# Minisumo_V1.net
KiCad netlist of a schematic drawn in EAGLE
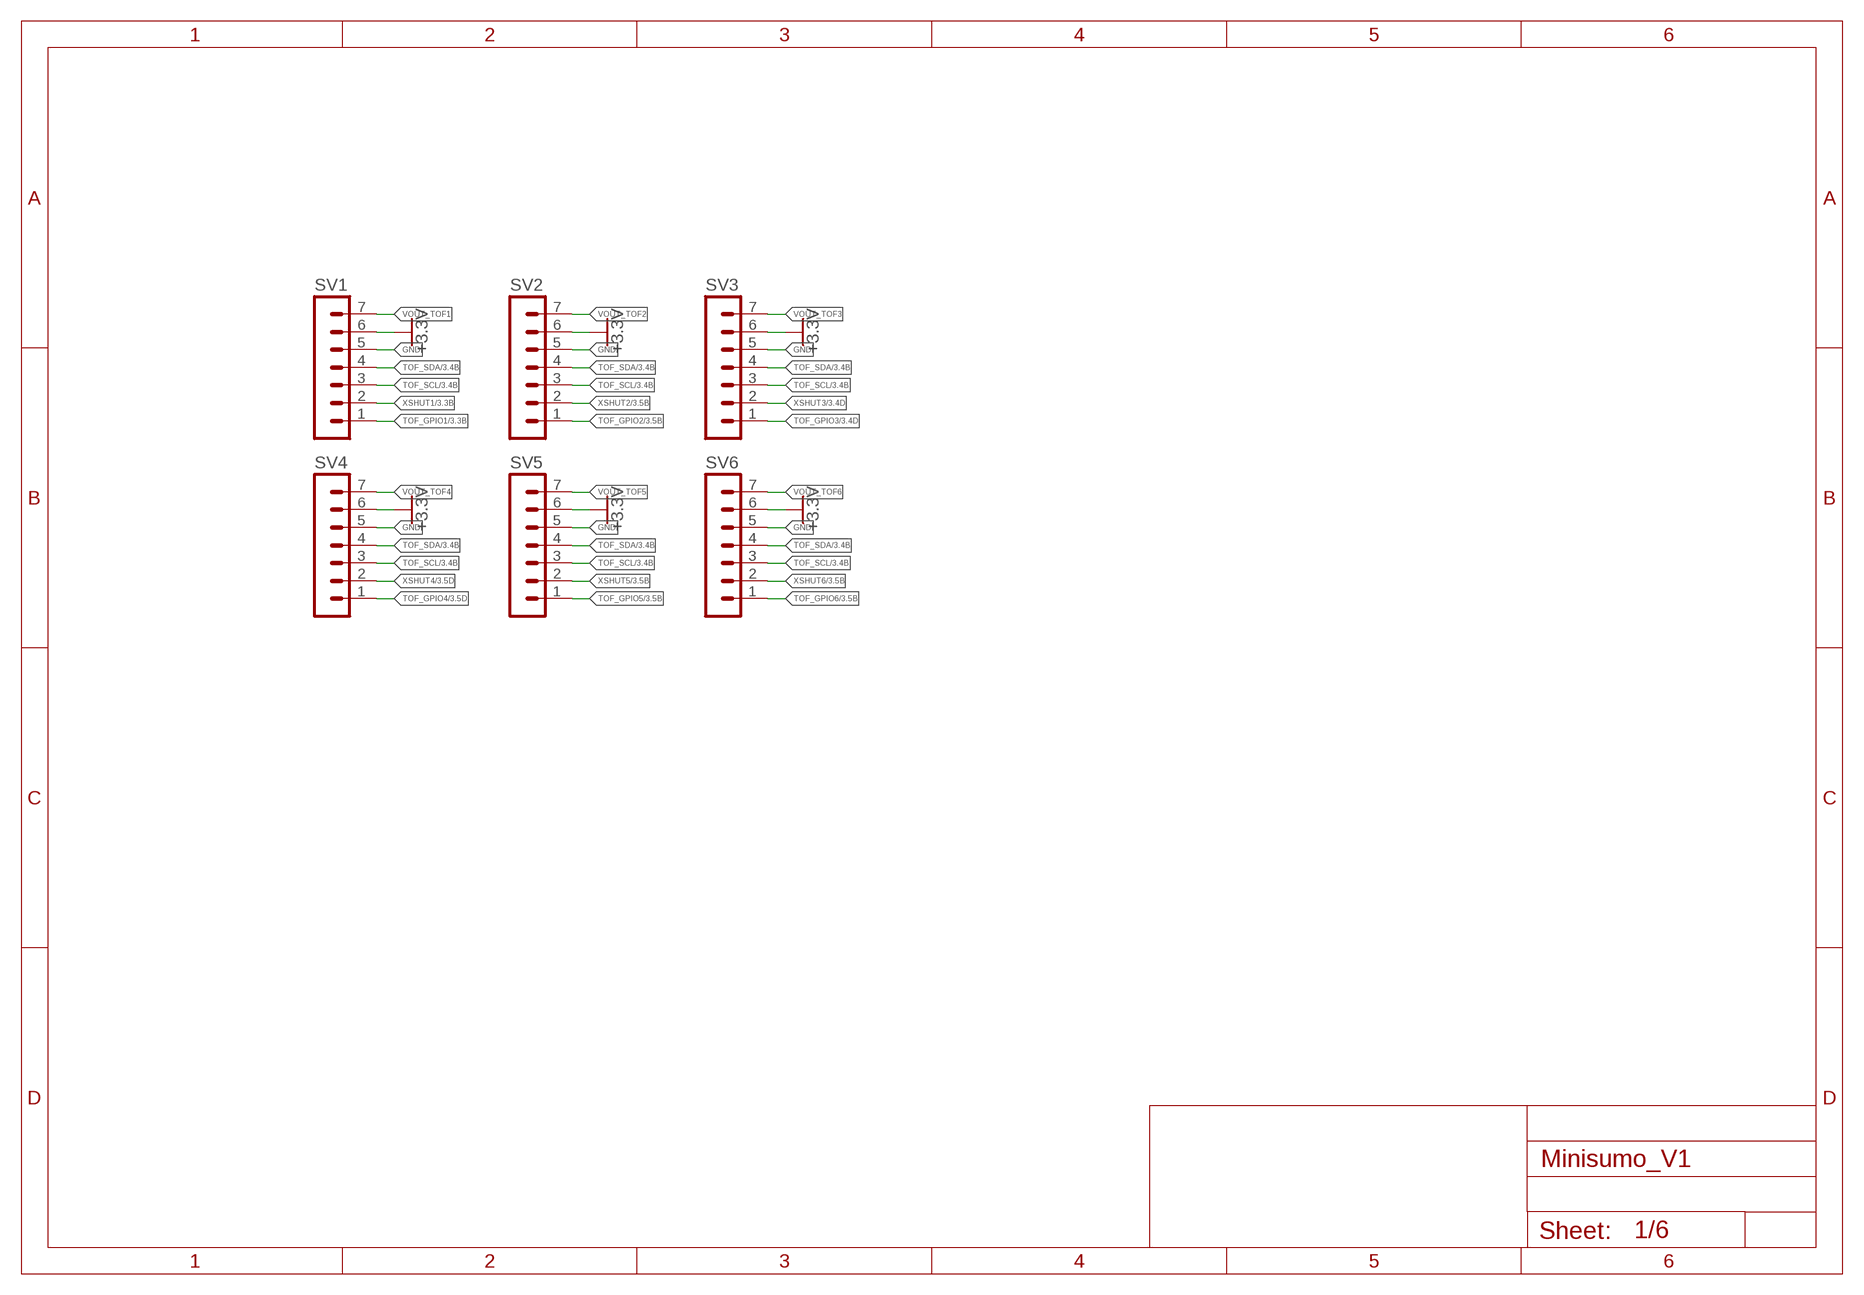
[diagram p0: schematic, sheet 1]
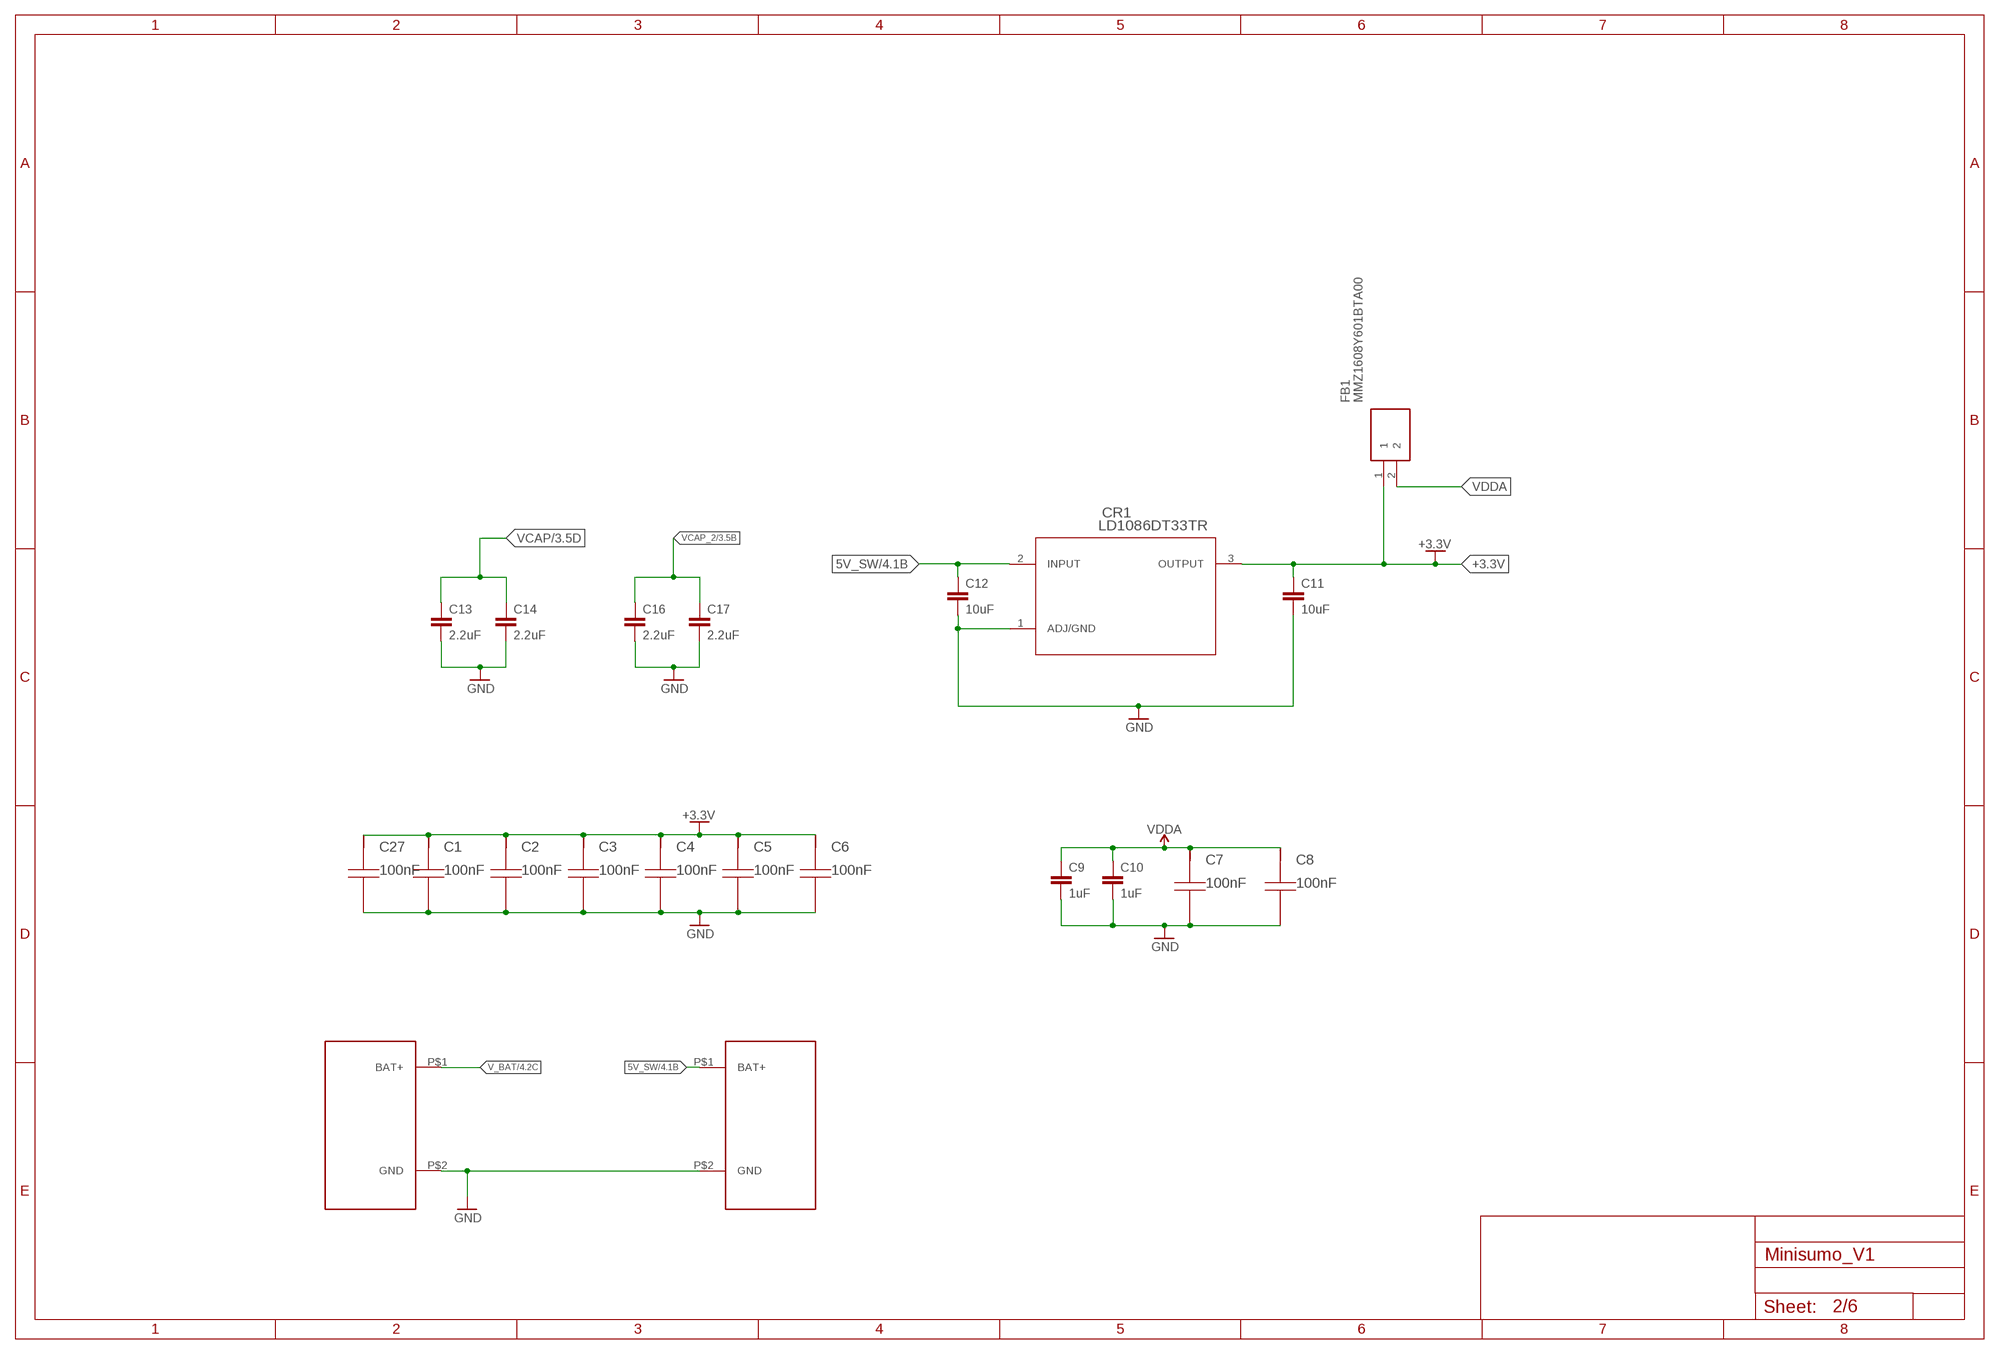
[diagram p1: schematic, sheet 2]
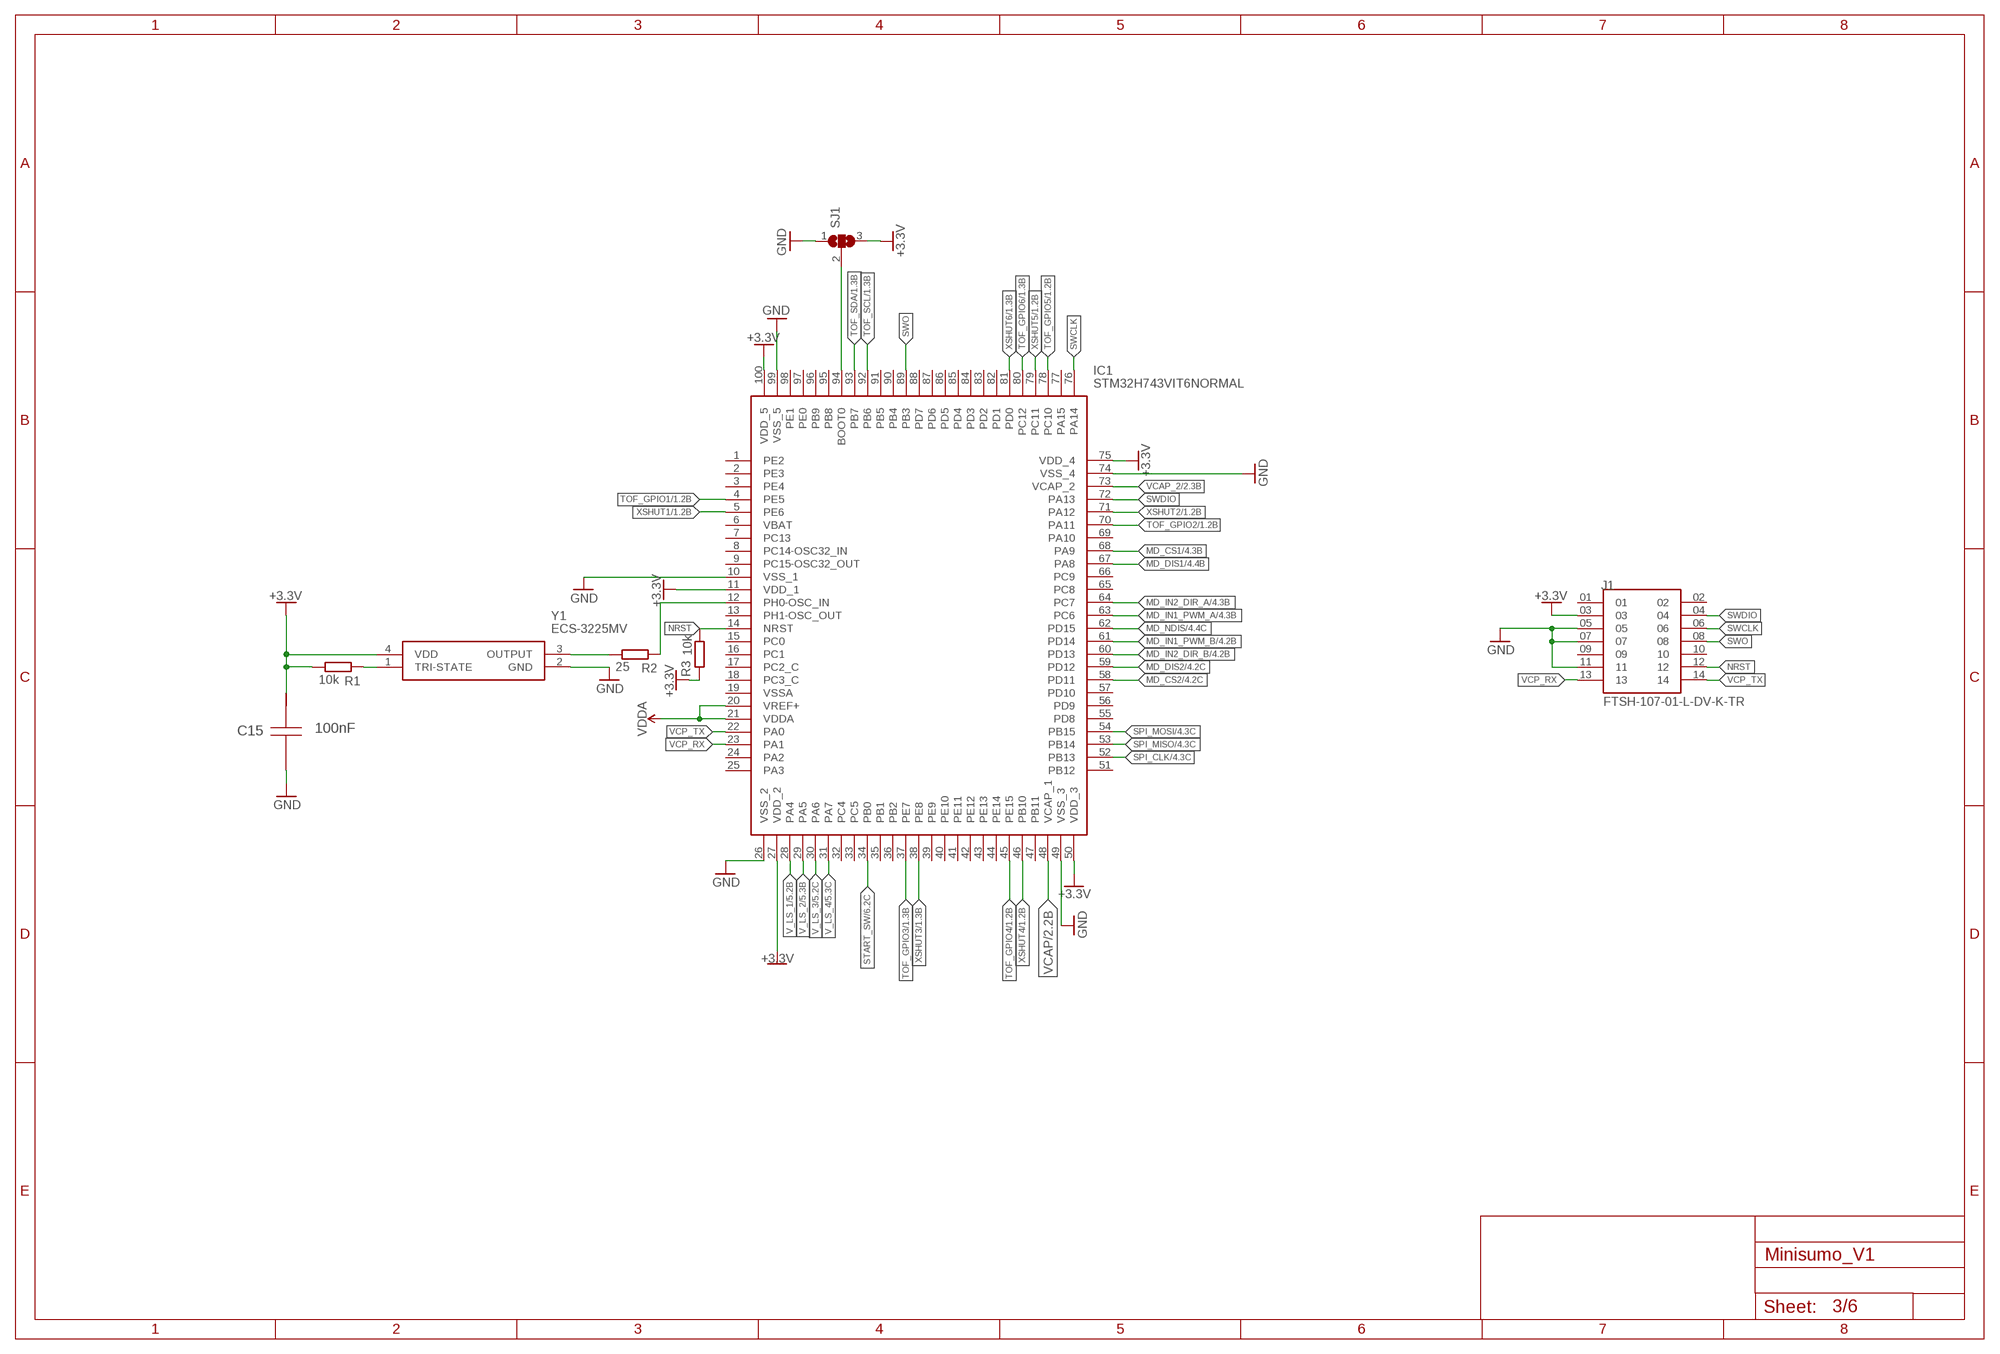
[diagram p2: schematic, sheet 3]
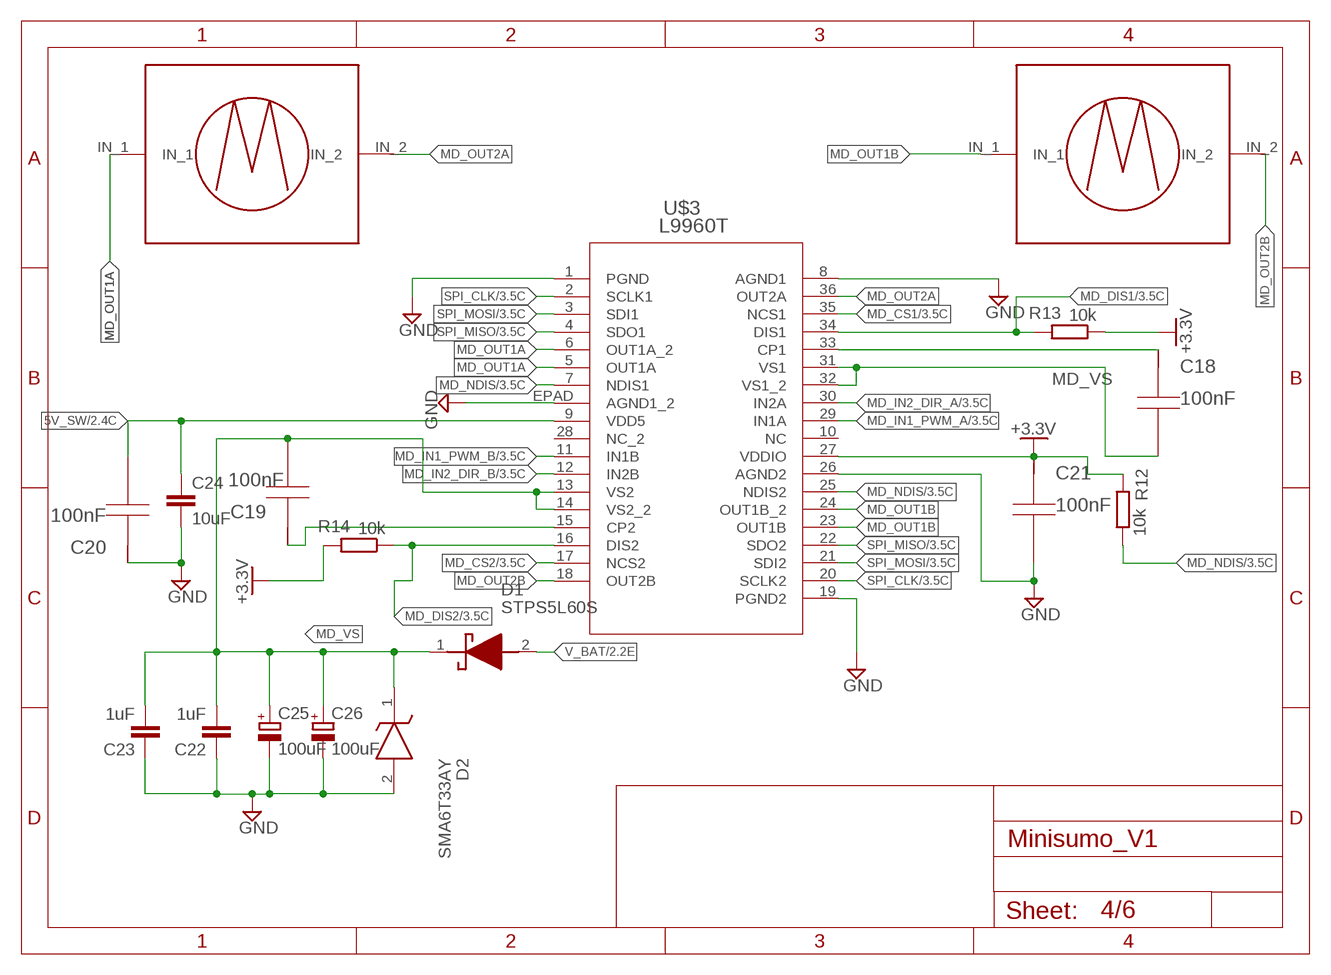
[diagram p3: schematic, sheet 4]
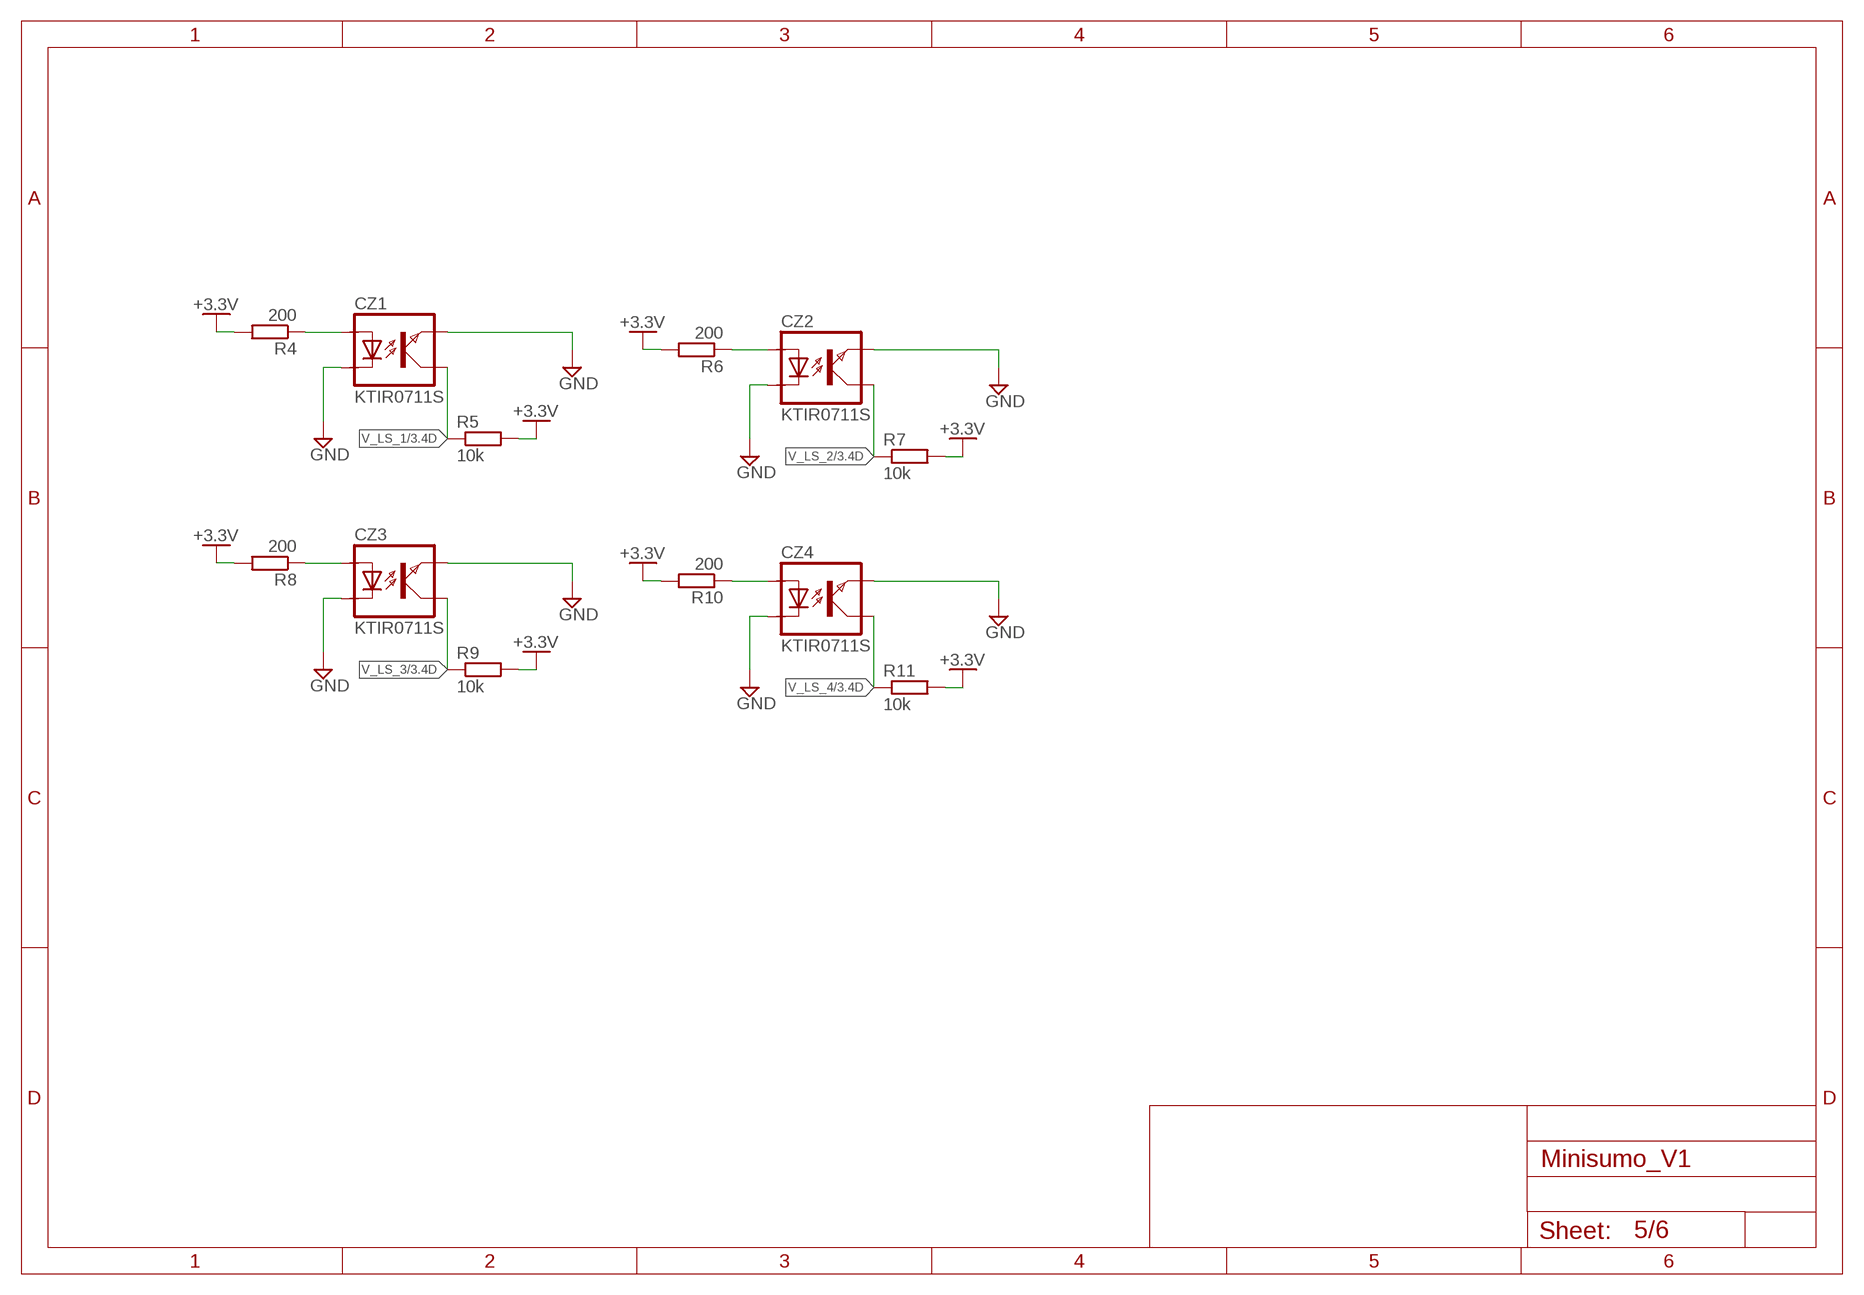
[diagram p4: schematic, sheet 5]
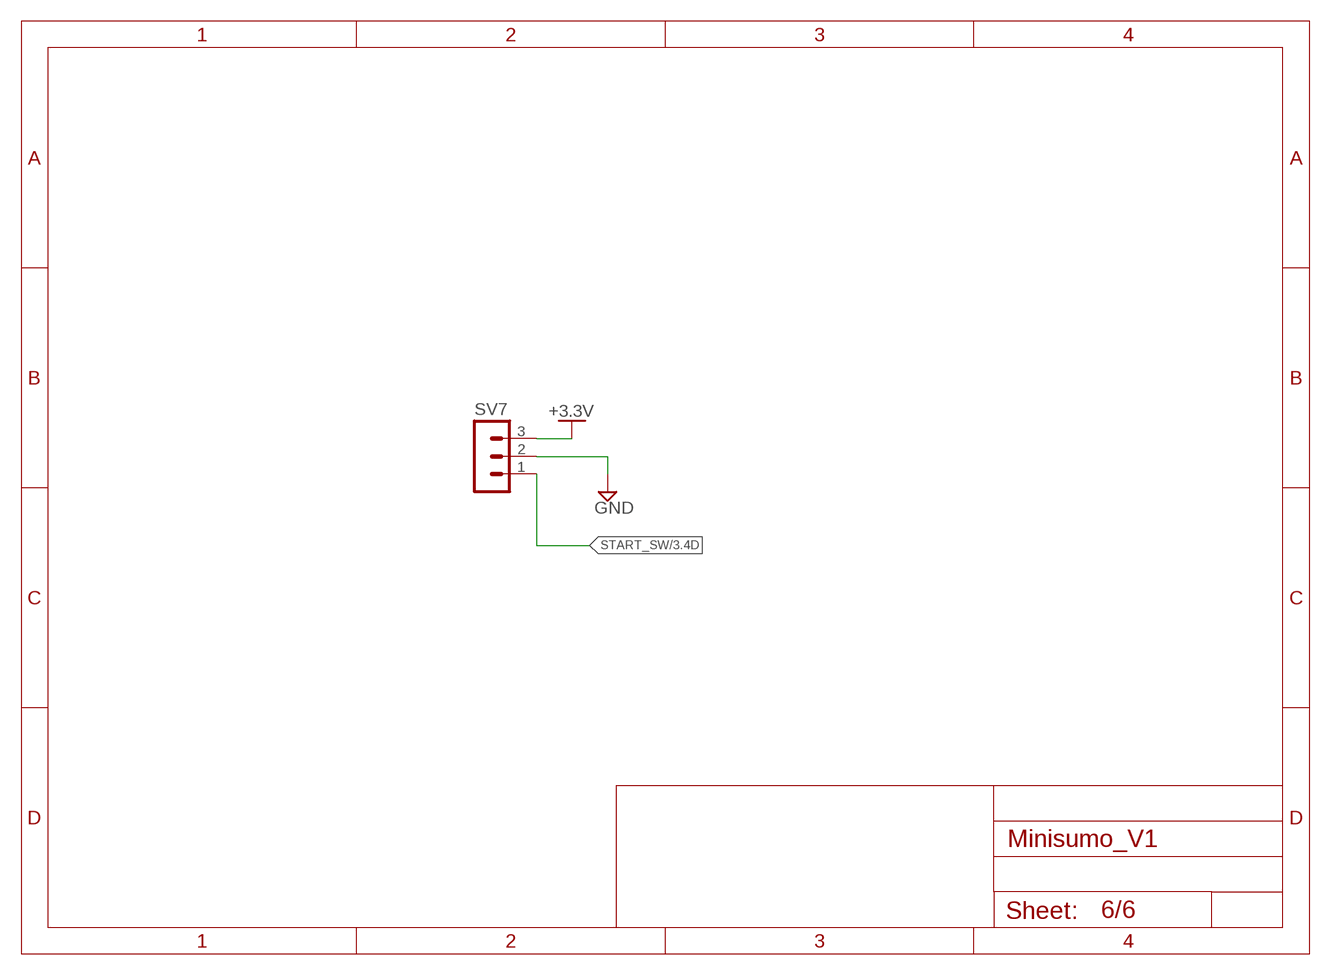
[diagram p5: schematic, sheet 6]

(export (version "E")
  (design (tool "Eeschema 10.0.6"))
  (components
    (comp (ref "SV7")
      (value "MA03-1")
      (footprint "eagle-import:MA03-1")
      (libsource (lib "eagle-import") (part "MA03-1"))
    )
    (comp (ref "SV1")
      (value "MA07-1")
      (footprint "eagle-import:MA07-1")
      (libsource (lib "eagle-import") (part "MA07-1"))
    )
    (comp (ref "SV2")
      (value "MA07-1")
      (footprint "eagle-import:MA07-1")
      (libsource (lib "eagle-import") (part "MA07-1"))
    )
    (comp (ref "SV3")
      (value "MA07-1")
      (footprint "eagle-import:MA07-1")
      (libsource (lib "eagle-import") (part "con-lstb_162_MA07-1"))
    )
    (comp (ref "SV4")
      (value "MA07-1")
      (footprint "eagle-import:MA07-1")
      (libsource (lib "eagle-import") (part "con-lstb_162_MA07-1"))
    )
    (comp (ref "SV5")
      (value "MA07-1")
      (footprint "eagle-import:MA07-1")
      (libsource (lib "eagle-import") (part "con-lstb_162_MA07-1"))
    )
    (comp (ref "SV6")
      (value "MA07-1")
      (footprint "eagle-import:MA07-1")
      (libsource (lib "eagle-import") (part "con-lstb_162_MA07-1"))
    )
    (comp (ref "CZ1")
      (value "KTIR0711S")
      (footprint "eagle-import:TOP")
      (fields (field (name "MANUFACTURER_PART_NO") "ITR8307/S18/TR8(B)"))
      (libsource (lib "eagle-import") (part "KTIR0711S"))
    )
    (comp (ref "CZ2")
      (value "KTIR0711S")
      (footprint "eagle-import:TOP")
      (fields (field (name "MANUFACTURER_PART_NO") "ITR8307/S18/TR8(B)"))
      (libsource (lib "eagle-import") (part "KTIR0711S"))
    )
    (comp (ref "CZ3")
      (value "KTIR0711S")
      (footprint "eagle-import:TOP")
      (fields (field (name "MANUFACTURER_PART_NO") "ITR8307/S18/TR8(B)"))
      (libsource (lib "eagle-import") (part "KTIR0711S"))
    )
    (comp (ref "CZ4")
      (value "KTIR0711S")
      (footprint "eagle-import:TOP")
      (fields (field (name "MANUFACTURER_PART_NO") "ITR8307/S18/TR8(B)"))
      (libsource (lib "eagle-import") (part "KTIR0711S"))
    )
    (comp (ref "R4")
      (value "200")
      (footprint "eagle-import:R0402")
      (libsource (lib "eagle-import") (part "R-EU_R0402"))
    )
    (comp (ref "R5")
      (value "10k")
      (footprint "eagle-import:R0402")
      (libsource (lib "eagle-import") (part "R-EU_R0402"))
    )
    (comp (ref "R6")
      (value "200")
      (footprint "eagle-import:R0402")
      (libsource (lib "eagle-import") (part "R-EU_R0402"))
    )
    (comp (ref "R7")
      (value "10k")
      (footprint "eagle-import:R0402")
      (libsource (lib "eagle-import") (part "R-EU_R0402"))
    )
    (comp (ref "R8")
      (value "200")
      (footprint "eagle-import:R0402")
      (libsource (lib "eagle-import") (part "R-EU_R0402"))
    )
    (comp (ref "R9")
      (value "10k")
      (footprint "eagle-import:R0402")
      (libsource (lib "eagle-import") (part "R-EU_R0402"))
    )
    (comp (ref "R10")
      (value "200")
      (footprint "eagle-import:R0402")
      (libsource (lib "eagle-import") (part "R-EU_R0402"))
    )
    (comp (ref "R11")
      (value "10k")
      (footprint "eagle-import:R0402")
      (libsource (lib "eagle-import") (part "R-EU_R0402"))
    )
    (comp (ref "C15")
      (value "100nF")
      (footprint "eagle-import:C0402")
      (libsource (lib "eagle-import") (part "GRM155R71C104KA88D0402"))
    )
    (comp (ref "IC1")
      (value "STM32H743VIT6NORMAL")
      (footprint "eagle-import:QFP50P1600X1600X160-100N")
      (libsource (lib "eagle-import") (part "STM32H743VIT6NORMAL"))
    )
    (comp (ref "J1")
      (value "FTSH-107-01-L-DV-K-TR")
      (footprint "eagle-import:SAMTEC_FTSH-107-01-L-DV-K-TR")
      (fields (field (name "MANUFACTURER") "Samtec"))
      (libsource (lib "eagle-import") (part "FTSH-107-01-L-DV-K-TR"))
    )
    (comp (ref "R1")
      (value "10k")
      (footprint "eagle-import:R0402")
      (libsource (lib "eagle-import") (part "R-EU_R0402"))
    )
    (comp (ref "R2")
      (value "25")
      (footprint "eagle-import:R0402")
      (libsource (lib "eagle-import") (part "R-EU_R0402"))
    )
    (comp (ref "R3")
      (value "10k")
      (footprint "eagle-import:R0402")
      (libsource (lib "eagle-import") (part "R-EU_R0402"))
    )
    (comp (ref "SJ1")
      (value "SJ2W")
      (footprint "eagle-import:SJ_2")
      (libsource (lib "eagle-import") (part "SJ2W"))
    )
    (comp (ref "Y1")
      (value "ECS-3225MV")
      (footprint "eagle-import:ECS3225MV")
      (libsource (lib "eagle-import") (part "ECS-3225MV"))
    )
    (comp (ref "C1")
      (value "100nF")
      (footprint "eagle-import:C0402")
      (libsource (lib "eagle-import") (part "GRM155R71C104KA88D0402"))
    )
    (comp (ref "C2")
      (value "100nF")
      (footprint "eagle-import:C0402")
      (libsource (lib "eagle-import") (part "GRM155R71C104KA88D0402"))
    )
    (comp (ref "C3")
      (value "100nF")
      (footprint "eagle-import:C0402")
      (libsource (lib "eagle-import") (part "GRM155R71C104KA88D0402"))
    )
    (comp (ref "C4")
      (value "100nF")
      (footprint "eagle-import:C0402")
      (libsource (lib "eagle-import") (part "GRM155R71C104KA88D0402"))
    )
    (comp (ref "C5")
      (value "100nF")
      (footprint "eagle-import:C0402")
      (libsource (lib "eagle-import") (part "GRM155R71C104KA88D0402"))
    )
    (comp (ref "C6")
      (value "100nF")
      (footprint "eagle-import:C0402")
      (libsource (lib "eagle-import") (part "GRM155R71C104KA88D0402"))
    )
    (comp (ref "C7")
      (value "100nF")
      (footprint "eagle-import:C0402")
      (libsource (lib "eagle-import") (part "GRM155R71C104KA88D0402"))
    )
    (comp (ref "C8")
      (value "100nF")
      (footprint "eagle-import:C0402")
      (libsource (lib "eagle-import") (part "GRM155R71C104KA88D0402"))
    )
    (comp (ref "C9")
      (value "1uF")
      (footprint "eagle-import:C0402")
      (fields (field (name "MANUFACTURER_PART_NO") "EMK105BJ105KV-F"))
      (libsource (lib "eagle-import") (part "C-EUC0402"))
    )
    (comp (ref "C10")
      (value "1uF")
      (footprint "eagle-import:C0402")
      (fields (field (name "MANUFACTURER_PART_NO") "EMK105BJ105KV-F"))
      (libsource (lib "eagle-import") (part "C-EUC0402"))
    )
    (comp (ref "C11")
      (value "10uF")
      (footprint "eagle-import:C0603")
      (fields (field (name "MANUFACTURER_PART_NO") "GRM188R61E106KA73D"))
      (libsource (lib "eagle-import") (part "C-EUC0603"))
    )
    (comp (ref "C12")
      (value "10uF")
      (footprint "eagle-import:C0603")
      (fields (field (name "MANUFACTURER_PART_NO") "GRM188R61E106KA73D"))
      (libsource (lib "eagle-import") (part "C-EUC0603"))
    )
    (comp (ref "C13")
      (value "2.2uF")
      (footprint "eagle-import:C0603")
      (fields (field (name "MANUFACTURER_PART_NO") "EMK107BJ225KA-T"))
      (libsource (lib "eagle-import") (part "C-EUC0603"))
    )
    (comp (ref "C14")
      (value "2.2uF")
      (footprint "eagle-import:C0603")
      (fields (field (name "MANUFACTURER_PART_NO") "GRM188R61E106KA73D"))
      (libsource (lib "eagle-import") (part "C-EUC0603"))
    )
    (comp (ref "C16")
      (value "2.2uF")
      (footprint "eagle-import:C0603")
      (fields (field (name "MANUFACTURER_PART_NO") "EMK107BJ225KA-T"))
      (libsource (lib "eagle-import") (part "C-EUC0603"))
    )
    (comp (ref "C17")
      (value "2.2uF")
      (footprint "eagle-import:C0603")
      (fields (field (name "MANUFACTURER_PART_NO") "GRM188R61E106KA73D"))
      (libsource (lib "eagle-import") (part "C-EUC0603"))
    )
    (comp (ref "C27")
      (value "100nF")
      (footprint "eagle-import:C0402")
      (libsource (lib "eagle-import") (part "GRM155R71C104KA88D0402"))
    )
    (comp (ref "CR1")
      (value "LD1086DT33TR")
      (footprint "eagle-import:D2PAK_STM")
      (fields (field (name "COPYRIGHT") "Copyright (C) 2021 Ultra Librarian. All rights reserved."))
      (libsource (lib "eagle-import") (part "LD1086DT33TR"))
    )
    (comp (ref "FB1")
      (value "MMZ1608Y601BTA00")
      (footprint "eagle-import:BEADC1608X95N")
      (fields (field (name "MOUSER_PART_NUMBER") "810-MMZ1608Y601BTA00"))
      (libsource (lib "eagle-import") (part "MMZ1608Y601BTA00"))
    )
    (comp (ref "U$6")
      (value "BAT_POW")
      (footprint "eagle-import:BAT_POW")
      (libsource (lib "eagle-import") (part "BAT_POW"))
    )
    (comp (ref "U$7")
      (value "BAT_POW")
      (footprint "eagle-import:BAT_POW")
      (libsource (lib "eagle-import") (part "BAT_POW"))
    )
    (comp (ref "C18")
      (value "100nF")
      (footprint "eagle-import:C0402")
      (libsource (lib "eagle-import") (part "GRM155R71C104KA88D0402"))
    )
    (comp (ref "C19")
      (value "100nF")
      (footprint "eagle-import:C0402")
      (libsource (lib "eagle-import") (part "GRM155R71C104KA88D0402"))
    )
    (comp (ref "C20")
      (value "100nF")
      (footprint "eagle-import:C0402")
      (libsource (lib "eagle-import") (part "GRM155R71C104KA88D0402"))
    )
    (comp (ref "C21")
      (value "100nF")
      (footprint "eagle-import:C0402")
      (libsource (lib "eagle-import") (part "GRM155R71C104KA88D0402"))
    )
    (comp (ref "C22")
      (value "1uF")
      (footprint "eagle-import:C0402")
      (fields (field (name "MANUFACTURER_PART_NO") "EMK105BJ105KV-F"))
      (libsource (lib "eagle-import") (part "C-EUC0402"))
    )
    (comp (ref "C23")
      (value "1uF")
      (footprint "eagle-import:C0402")
      (fields (field (name "MANUFACTURER_PART_NO") "EMK105BJ105KV-F"))
      (libsource (lib "eagle-import") (part "C-EUC0402"))
    )
    (comp (ref "C24")
      (value "10uF")
      (footprint "eagle-import:C1210")
      (fields (field (name "MANUFACTURER_PART_NO") "UMK325AB7106KMHP"))
      (libsource (lib "eagle-import") (part "C-EUC1210"))
    )
    (comp (ref "C25")
      (value "100uF")
      (footprint "eagle-import:UD-8X10_NICHICON")
      (fields (field (name "MANUFACTURER_PART_NO") "RVT1H101M0810"))
      (libsource (lib "eagle-import") (part "CPOL-EUUD-8X10"))
    )
    (comp (ref "C26")
      (value "100uF")
      (footprint "eagle-import:UD-8X10_NICHICON")
      (fields (field (name "MANUFACTURER_PART_NO") "RVT1H101M0810"))
      (libsource (lib "eagle-import") (part "CPOL-EUUD-8X10"))
    )
    (comp (ref "D1")
      (value "STPS5L60S")
      (footprint "eagle-import:DIOM8059X265N")
      (fields (field (name "MOUSER_PART_NUMBER") "511-STPS5L60S"))
      (libsource (lib "eagle-import") (part "STPS5L60S"))
    )
    (comp (ref "D2")
      (value "SMA6T33AY")
      (footprint "eagle-import:DIOM5126X265N")
      (fields (field (name "MOUSER_PART_NUMBER") "511-SMA6T33AY"))
      (libsource (lib "eagle-import") (part "SMA6T33AY"))
    )
    (comp (ref "R12")
      (value "10k")
      (footprint "eagle-import:R0402")
      (libsource (lib "eagle-import") (part "R-EU_R0402"))
    )
    (comp (ref "R13")
      (value "10k")
      (footprint "eagle-import:R0402")
      (libsource (lib "eagle-import") (part "R-EU_R0402"))
    )
    (comp (ref "R14")
      (value "10k")
      (footprint "eagle-import:R0402")
      (libsource (lib "eagle-import") (part "R-EU_R0402"))
    )
    (comp (ref "U$3")
      (value "L9960T")
      (footprint "eagle-import:POWERSSO-36_STM")
      (libsource (lib "eagle-import") (part "L9960T"))
    )
    (comp (ref "U$4")
      (value "MD_OUT")
      (footprint "eagle-import:MD_OUT")
      (libsource (lib "eagle-import") (part "MD_OUT"))
    )
    (comp (ref "U$5")
      (value "MD_OUT")
      (footprint "eagle-import:MD_OUT")
      (libsource (lib "eagle-import") (part "MD_OUT"))
    )
  )
  (nets
    (net (code "1") (name "+3.3V") (class "Default")
      (node (ref "C1") (pin "1") (pinfunction "1_1") (pintype "passive"))
      (node (ref "C11") (pin "1") (pinfunction "1_1") (pintype "passive"))
      (node (ref "C15") (pin "1") (pinfunction "1_1") (pintype "passive"))
      (node (ref "C2") (pin "1") (pinfunction "1_1") (pintype "passive"))
      (node (ref "C21") (pin "1") (pinfunction "1_1") (pintype "passive"))
      (node (ref "C27") (pin "1") (pinfunction "1_1") (pintype "passive"))
      (node (ref "C3") (pin "1") (pinfunction "1_1") (pintype "passive"))
      (node (ref "C4") (pin "1") (pinfunction "1_1") (pintype "passive"))
      (node (ref "C5") (pin "1") (pinfunction "1_1") (pintype "passive"))
      (node (ref "C6") (pin "1") (pinfunction "1_1") (pintype "passive"))
      (node (ref "CR1") (pin "3") (pinfunction "OUTPUT_3") (pintype "output"))
      (node (ref "FB1") (pin "1") (pinfunction "1_1") (pintype "bidirectional"))
      (node (ref "IC1") (pin "100") (pinfunction "VDD_5_100") (pintype "bidirectional"))
      (node (ref "IC1") (pin "11") (pinfunction "VDD_1_11") (pintype "bidirectional"))
      (node (ref "IC1") (pin "27") (pinfunction "VDD_2_27") (pintype "bidirectional"))
      (node (ref "IC1") (pin "50") (pinfunction "VDD_3_50") (pintype "bidirectional"))
      (node (ref "IC1") (pin "75") (pinfunction "VDD_4_75") (pintype "bidirectional"))
      (node (ref "J1") (pin "03") (pinfunction "03_03") (pintype "passive"))
      (node (ref "R1") (pin "1") (pinfunction "1_1") (pintype "passive"))
      (node (ref "R10") (pin "2") (pinfunction "2_2") (pintype "passive"))
      (node (ref "R11") (pin "2") (pinfunction "2_2") (pintype "passive"))
      (node (ref "R12") (pin "2") (pinfunction "2_2") (pintype "passive"))
      (node (ref "R13") (pin "1") (pinfunction "1_1") (pintype "passive"))
      (node (ref "R14") (pin "2") (pinfunction "2_2") (pintype "passive"))
      (node (ref "R3") (pin "2") (pinfunction "2_2") (pintype "passive"))
      (node (ref "R4") (pin "2") (pinfunction "2_2") (pintype "passive"))
      (node (ref "R5") (pin "2") (pinfunction "2_2") (pintype "passive"))
      (node (ref "R6") (pin "2") (pinfunction "2_2") (pintype "passive"))
      (node (ref "R7") (pin "2") (pinfunction "2_2") (pintype "passive"))
      (node (ref "R8") (pin "2") (pinfunction "2_2") (pintype "passive"))
      (node (ref "R9") (pin "2") (pinfunction "2_2") (pintype "passive"))
      (node (ref "SJ1") (pin "3") (pinfunction "3_3") (pintype "passive"))
      (node (ref "SV1") (pin "6") (pinfunction "6_6") (pintype "passive"))
      (node (ref "SV2") (pin "6") (pinfunction "6_6") (pintype "passive"))
      (node (ref "SV3") (pin "6") (pinfunction "6_6") (pintype "passive"))
      (node (ref "SV4") (pin "6") (pinfunction "6_6") (pintype "passive"))
      (node (ref "SV5") (pin "6") (pinfunction "6_6") (pintype "passive"))
      (node (ref "SV6") (pin "6") (pinfunction "6_6") (pintype "passive"))
      (node (ref "SV7") (pin "3") (pinfunction "3_3") (pintype "passive"))
      (node (ref "U$3") (pin "27") (pinfunction "VDDIO_27") (pintype "power_in"))
      (node (ref "Y1") (pin "4") (pinfunction "VDD_4") (pintype "bidirectional"))
    )
    (net (code "2") (name "5V_SW") (class "Default")
      (node (ref "C12") (pin "1") (pinfunction "1_1") (pintype "passive"))
      (node (ref "C20") (pin "2") (pinfunction "2_2") (pintype "passive"))
      (node (ref "C24") (pin "1") (pinfunction "1_1") (pintype "passive"))
      (node (ref "CR1") (pin "2") (pinfunction "INPUT_2") (pintype "input"))
      (node (ref "U$3") (pin "9") (pinfunction "VDD5_9") (pintype "power_in"))
      (node (ref "U$7") (pin "P$1") (pinfunction "BAT+_P$1") (pintype "bidirectional"))
    )
    (net (code "3") (name "GND") (class "Default")
      (node (ref "C1") (pin "2") (pinfunction "2_2") (pintype "passive"))
      (node (ref "C10") (pin "2") (pinfunction "2_2") (pintype "passive"))
      (node (ref "C11") (pin "2") (pinfunction "2_2") (pintype "passive"))
      (node (ref "C12") (pin "2") (pinfunction "2_2") (pintype "passive"))
      (node (ref "C13") (pin "2") (pinfunction "2_2") (pintype "passive"))
      (node (ref "C14") (pin "2") (pinfunction "2_2") (pintype "passive"))
      (node (ref "C15") (pin "2") (pinfunction "2_2") (pintype "passive"))
      (node (ref "C16") (pin "2") (pinfunction "2_2") (pintype "passive"))
      (node (ref "C17") (pin "2") (pinfunction "2_2") (pintype "passive"))
      (node (ref "C2") (pin "2") (pinfunction "2_2") (pintype "passive"))
      (node (ref "C20") (pin "1") (pinfunction "1_1") (pintype "passive"))
      (node (ref "C21") (pin "2") (pinfunction "2_2") (pintype "passive"))
      (node (ref "C22") (pin "1") (pinfunction "1_1") (pintype "passive"))
      (node (ref "C23") (pin "1") (pinfunction "1_1") (pintype "passive"))
      (node (ref "C24") (pin "2") (pinfunction "2_2") (pintype "passive"))
      (node (ref "C25") (pin "-") (pinfunction "-_-") (pintype "passive"))
      (node (ref "C26") (pin "-") (pinfunction "-_-") (pintype "passive"))
      (node (ref "C27") (pin "2") (pinfunction "2_2") (pintype "passive"))
      (node (ref "C3") (pin "2") (pinfunction "2_2") (pintype "passive"))
      (node (ref "C4") (pin "2") (pinfunction "2_2") (pintype "passive"))
      (node (ref "C5") (pin "2") (pinfunction "2_2") (pintype "passive"))
      (node (ref "C6") (pin "2") (pinfunction "2_2") (pintype "passive"))
      (node (ref "C7") (pin "2") (pinfunction "2_2") (pintype "passive"))
      (node (ref "C8") (pin "2") (pinfunction "2_2") (pintype "passive"))
      (node (ref "C9") (pin "2") (pinfunction "2_2") (pintype "passive"))
      (node (ref "CR1") (pin "1") (pinfunction "ADJ/GND_1") (pintype "passive"))
      (node (ref "CZ1") (pin "EMITER") (pinfunction "EMITER_EMITER") (pintype "bidirectional"))
      (node (ref "CZ1") (pin "KATODA") (pinfunction "KATODA_KATODA") (pintype "passive"))
      (node (ref "CZ2") (pin "EMITER") (pinfunction "EMITER_EMITER") (pintype "bidirectional"))
      (node (ref "CZ2") (pin "KATODA") (pinfunction "KATODA_KATODA") (pintype "passive"))
      (node (ref "CZ3") (pin "EMITER") (pinfunction "EMITER_EMITER") (pintype "bidirectional"))
      (node (ref "CZ3") (pin "KATODA") (pinfunction "KATODA_KATODA") (pintype "passive"))
      (node (ref "CZ4") (pin "EMITER") (pinfunction "EMITER_EMITER") (pintype "bidirectional"))
      (node (ref "CZ4") (pin "KATODA") (pinfunction "KATODA_KATODA") (pintype "passive"))
      (node (ref "D2") (pin "2") (pinfunction "A_2") (pintype "bidirectional"))
      (node (ref "IC1") (pin "10") (pinfunction "VSS_1_10") (pintype "bidirectional"))
      (node (ref "IC1") (pin "26") (pinfunction "VSS_2_26") (pintype "bidirectional"))
      (node (ref "IC1") (pin "49") (pinfunction "VSS_3_49") (pintype "bidirectional"))
      (node (ref "IC1") (pin "74") (pinfunction "VSS_4_74") (pintype "bidirectional"))
      (node (ref "IC1") (pin "99") (pinfunction "VSS_5_99") (pintype "bidirectional"))
      (node (ref "J1") (pin "05") (pinfunction "05_05") (pintype "passive"))
      (node (ref "J1") (pin "07") (pinfunction "07_07") (pintype "passive"))
      (node (ref "J1") (pin "11") (pinfunction "11_11") (pintype "passive"))
      (node (ref "SJ1") (pin "1") (pinfunction "1_1") (pintype "passive"))
      (node (ref "SV1") (pin "5") (pinfunction "5_5") (pintype "passive"))
      (node (ref "SV2") (pin "5") (pinfunction "5_5") (pintype "passive"))
      (node (ref "SV3") (pin "5") (pinfunction "5_5") (pintype "passive"))
      (node (ref "SV4") (pin "5") (pinfunction "5_5") (pintype "passive"))
      (node (ref "SV5") (pin "5") (pinfunction "5_5") (pintype "passive"))
      (node (ref "SV6") (pin "5") (pinfunction "5_5") (pintype "passive"))
      (node (ref "SV7") (pin "2") (pinfunction "2_2") (pintype "passive"))
      (node (ref "U$3") (pin "1") (pinfunction "PGND_1") (pintype "passive"))
      (node (ref "U$3") (pin "19") (pinfunction "PGND2_19") (pintype "passive"))
      (node (ref "U$3") (pin "26") (pinfunction "AGND2_26") (pintype "passive"))
      (node (ref "U$3") (pin "8") (pinfunction "AGND1_8") (pintype "passive"))
      (node (ref "U$3") (pin "EPAD") (pinfunction "AGND1_2_EPAD") (pintype "passive"))
      (node (ref "U$6") (pin "P$2") (pinfunction "GND_P$2") (pintype "bidirectional"))
      (node (ref "U$7") (pin "P$2") (pinfunction "GND_P$2") (pintype "bidirectional"))
      (node (ref "Y1") (pin "2") (pinfunction "GND_2") (pintype "bidirectional"))
    )
    (net (code "4") (name "MD_CS1") (class "Default")
      (node (ref "IC1") (pin "68") (pinfunction "PA9_68") (pintype "bidirectional"))
      (node (ref "U$3") (pin "35") (pinfunction "NCS1_35") (pintype "input"))
    )
    (net (code "5") (name "MD_CS2") (class "Default")
      (node (ref "IC1") (pin "58") (pinfunction "PD11_58") (pintype "bidirectional"))
      (node (ref "U$3") (pin "17") (pinfunction "NCS2_17") (pintype "input"))
    )
    (net (code "6") (name "MD_DIS1") (class "Default")
      (node (ref "IC1") (pin "67") (pinfunction "PA8_67") (pintype "bidirectional"))
      (node (ref "R13") (pin "2") (pinfunction "2_2") (pintype "passive"))
      (node (ref "U$3") (pin "34") (pinfunction "DIS1_34") (pintype "input"))
    )
    (net (code "7") (name "MD_DIS2") (class "Default")
      (node (ref "IC1") (pin "59") (pinfunction "PD12_59") (pintype "bidirectional"))
      (node (ref "R14") (pin "1") (pinfunction "1_1") (pintype "passive"))
      (node (ref "U$3") (pin "16") (pinfunction "DIS2_16") (pintype "input"))
    )
    (net (code "8") (name "MD_IN1_PWM_A") (class "Default")
      (node (ref "IC1") (pin "63") (pinfunction "PC6_63") (pintype "bidirectional"))
      (node (ref "U$3") (pin "29") (pinfunction "IN1A_29") (pintype "input"))
    )
    (net (code "9") (name "MD_IN1_PWM_B") (class "Default")
      (node (ref "IC1") (pin "61") (pinfunction "PD14_61") (pintype "bidirectional"))
      (node (ref "U$3") (pin "11") (pinfunction "IN1B_11") (pintype "input"))
    )
    (net (code "10") (name "MD_IN2_DIR_A") (class "Default")
      (node (ref "IC1") (pin "64") (pinfunction "PC7_64") (pintype "bidirectional"))
      (node (ref "U$3") (pin "30") (pinfunction "IN2A_30") (pintype "input"))
    )
    (net (code "11") (name "MD_IN2_DIR_B") (class "Default")
      (node (ref "IC1") (pin "60") (pinfunction "PD13_60") (pintype "bidirectional"))
      (node (ref "U$3") (pin "12") (pinfunction "IN2B_12") (pintype "input"))
    )
    (net (code "12") (name "MD_NDIS") (class "Default")
      (node (ref "IC1") (pin "62") (pinfunction "PD15_62") (pintype "bidirectional"))
      (node (ref "R12") (pin "1") (pinfunction "1_1") (pintype "passive"))
      (node (ref "U$3") (pin "25") (pinfunction "NDIS2_25") (pintype "bidirectional"))
      (node (ref "U$3") (pin "7") (pinfunction "NDIS1_7") (pintype "bidirectional"))
    )
    (net (code "13") (name "MD_OUT1A") (class "Default")
      (node (ref "U$3") (pin "5") (pinfunction "OUT1A_5") (pintype "output"))
      (node (ref "U$3") (pin "6") (pinfunction "OUT1A_2_6") (pintype "output"))
      (node (ref "U$4") (pin "IN_1") (pinfunction "IN_1_IN_1") (pintype "bidirectional"))
    )
    (net (code "14") (name "MD_OUT1B") (class "Default")
      (node (ref "U$3") (pin "23") (pinfunction "OUT1B_23") (pintype "output"))
      (node (ref "U$3") (pin "24") (pinfunction "OUT1B_2_24") (pintype "output"))
      (node (ref "U$5") (pin "IN_1") (pinfunction "IN_1_IN_1") (pintype "bidirectional"))
    )
    (net (code "15") (name "MD_OUT2A") (class "Default")
      (node (ref "U$3") (pin "36") (pinfunction "OUT2A_36") (pintype "output"))
      (node (ref "U$4") (pin "IN_2") (pinfunction "IN_2_IN_2") (pintype "bidirectional"))
    )
    (net (code "16") (name "MD_OUT2B") (class "Default")
      (node (ref "U$3") (pin "18") (pinfunction "OUT2B_18") (pintype "output"))
      (node (ref "U$5") (pin "IN_2") (pinfunction "IN_2_IN_2") (pintype "bidirectional"))
    )
    (net (code "17") (name "MD_VS") (class "Default")
      (node (ref "C18") (pin "2") (pinfunction "2_2") (pintype "passive"))
      (node (ref "C19") (pin "2") (pinfunction "2_2") (pintype "passive"))
      (node (ref "C22") (pin "2") (pinfunction "2_2") (pintype "passive"))
      (node (ref "C23") (pin "2") (pinfunction "2_2") (pintype "passive"))
      (node (ref "C25") (pin "+") (pinfunction "+_+") (pintype "passive"))
      (node (ref "C26") (pin "+") (pinfunction "+_+") (pintype "passive"))
      (node (ref "D1") (pin "1") (pinfunction "K_1") (pintype "bidirectional"))
      (node (ref "D2") (pin "1") (pinfunction "K_1") (pintype "bidirectional"))
      (node (ref "U$3") (pin "13") (pinfunction "VS2_13") (pintype "input"))
      (node (ref "U$3") (pin "14") (pinfunction "VS2_2_14") (pintype "input"))
      (node (ref "U$3") (pin "31") (pinfunction "VS1_31") (pintype "power_in"))
      (node (ref "U$3") (pin "32") (pinfunction "VS1_2_32") (pintype "power_in"))
    )
    (net (code "18") (name "NRST") (class "Default")
      (node (ref "IC1") (pin "14") (pinfunction "NRST_14") (pintype "bidirectional"))
      (node (ref "J1") (pin "12") (pinfunction "12_12") (pintype "passive"))
      (node (ref "R3") (pin "1") (pinfunction "1_1") (pintype "passive"))
    )
    (net (code "19") (name "Net-(CZ1-PadANODA)") (class "Default")
      (node (ref "CZ1") (pin "ANODA") (pinfunction "ANODA_ANODA") (pintype "passive"))
      (node (ref "R4") (pin "1") (pinfunction "1_1") (pintype "passive"))
    )
    (net (code "20") (name "Net-(CZ2-PadANODA)") (class "Default")
      (node (ref "CZ2") (pin "ANODA") (pinfunction "ANODA_ANODA") (pintype "passive"))
      (node (ref "R6") (pin "1") (pinfunction "1_1") (pintype "passive"))
    )
    (net (code "21") (name "Net-(CZ3-PadANODA)") (class "Default")
      (node (ref "CZ3") (pin "ANODA") (pinfunction "ANODA_ANODA") (pintype "passive"))
      (node (ref "R8") (pin "1") (pinfunction "1_1") (pintype "passive"))
    )
    (net (code "22") (name "Net-(CZ4-PadANODA)") (class "Default")
      (node (ref "CZ4") (pin "ANODA") (pinfunction "ANODA_ANODA") (pintype "passive"))
      (node (ref "R10") (pin "1") (pinfunction "1_1") (pintype "passive"))
    )
    (net (code "23") (name "Net-(IC1-BOOT0)") (class "Default")
      (node (ref "IC1") (pin "94") (pinfunction "BOOT0_94") (pintype "bidirectional"))
      (node (ref "SJ1") (pin "2") (pinfunction "2_2") (pintype "passive"))
    )
    (net (code "24") (name "Net-(IC1-PH0-OSC_IN)") (class "Default")
      (node (ref "IC1") (pin "12") (pinfunction "PH0-OSC_IN_12") (pintype "bidirectional"))
      (node (ref "R2") (pin "2") (pinfunction "2_2") (pintype "passive"))
    )
    (net (code "25") (name "Net-(U$3-CP1)") (class "Default")
      (node (ref "C18") (pin "1") (pinfunction "1_1") (pintype "passive"))
      (node (ref "U$3") (pin "33") (pinfunction "CP1_33") (pintype "output"))
    )
    (net (code "26") (name "Net-(U$3-CP2)") (class "Default")
      (node (ref "C19") (pin "1") (pinfunction "1_1") (pintype "passive"))
      (node (ref "U$3") (pin "15") (pinfunction "CP2_15") (pintype "output"))
    )
    (net (code "27") (name "Net-(Y1-OUTPUT)") (class "Default")
      (node (ref "R2") (pin "1") (pinfunction "1_1") (pintype "passive"))
      (node (ref "Y1") (pin "3") (pinfunction "OUTPUT_3") (pintype "bidirectional"))
    )
    (net (code "28") (name "Net-(Y1-TRI-STATE)") (class "Default")
      (node (ref "R1") (pin "2") (pinfunction "2_2") (pintype "passive"))
      (node (ref "Y1") (pin "1") (pinfunction "TRI-STATE_1") (pintype "bidirectional"))
    )
    (net (code "29") (name "SPI_CLK") (class "Default")
      (node (ref "IC1") (pin "52") (pinfunction "PB13_52") (pintype "bidirectional"))
      (node (ref "U$3") (pin "2") (pinfunction "SCLK1_2") (pintype "input"))
      (node (ref "U$3") (pin "20") (pinfunction "SCLK2_20") (pintype "input"))
    )
    (net (code "30") (name "SPI_MISO") (class "Default")
      (node (ref "IC1") (pin "53") (pinfunction "PB14_53") (pintype "bidirectional"))
      (node (ref "U$3") (pin "22") (pinfunction "SDO2_22") (pintype "output"))
      (node (ref "U$3") (pin "4") (pinfunction "SDO1_4") (pintype "output"))
    )
    (net (code "31") (name "SPI_MOSI") (class "Default")
      (node (ref "IC1") (pin "54") (pinfunction "PB15_54") (pintype "bidirectional"))
      (node (ref "U$3") (pin "21") (pinfunction "SDI2_21") (pintype "input"))
      (node (ref "U$3") (pin "3") (pinfunction "SDI1_3") (pintype "input"))
    )
    (net (code "32") (name "START_SW") (class "Default")
      (node (ref "IC1") (pin "34") (pinfunction "PB0_34") (pintype "bidirectional"))
      (node (ref "SV7") (pin "1") (pinfunction "1_1") (pintype "passive"))
    )
    (net (code "33") (name "SWCLK") (class "Default")
      (node (ref "IC1") (pin "76") (pinfunction "PA14_76") (pintype "bidirectional"))
      (node (ref "J1") (pin "06") (pinfunction "06_06") (pintype "passive"))
    )
    (net (code "34") (name "SWDIO") (class "Default")
      (node (ref "IC1") (pin "72") (pinfunction "PA13_72") (pintype "bidirectional"))
      (node (ref "J1") (pin "04") (pinfunction "04_04") (pintype "passive"))
    )
    (net (code "35") (name "SWO") (class "Default")
      (node (ref "IC1") (pin "89") (pinfunction "PB3_89") (pintype "bidirectional"))
      (node (ref "J1") (pin "08") (pinfunction "08_08") (pintype "passive"))
    )
    (net (code "36") (name "TOF_GPIO1") (class "Default")
      (node (ref "IC1") (pin "4") (pinfunction "PE5_4") (pintype "bidirectional"))
      (node (ref "SV1") (pin "1") (pinfunction "1_1") (pintype "passive"))
    )
    (net (code "37") (name "TOF_GPIO2") (class "Default")
      (node (ref "IC1") (pin "70") (pinfunction "PA11_70") (pintype "bidirectional"))
      (node (ref "SV2") (pin "1") (pinfunction "1_1") (pintype "passive"))
    )
    (net (code "38") (name "TOF_GPIO3") (class "Default")
      (node (ref "IC1") (pin "37") (pinfunction "PE7_37") (pintype "bidirectional"))
      (node (ref "SV3") (pin "1") (pinfunction "1_1") (pintype "passive"))
    )
    (net (code "39") (name "TOF_GPIO4") (class "Default")
      (node (ref "IC1") (pin "45") (pinfunction "PE15_45") (pintype "bidirectional"))
      (node (ref "SV4") (pin "1") (pinfunction "1_1") (pintype "passive"))
    )
    (net (code "40") (name "TOF_GPIO5") (class "Default")
      (node (ref "IC1") (pin "78") (pinfunction "PC10_78") (pintype "bidirectional"))
      (node (ref "SV5") (pin "1") (pinfunction "1_1") (pintype "passive"))
    )
    (net (code "41") (name "TOF_GPIO6") (class "Default")
      (node (ref "IC1") (pin "80") (pinfunction "PC12_80") (pintype "bidirectional"))
      (node (ref "SV6") (pin "1") (pinfunction "1_1") (pintype "passive"))
    )
    (net (code "42") (name "TOF_SCL") (class "Default")
      (node (ref "IC1") (pin "92") (pinfunction "PB6_92") (pintype "bidirectional"))
      (node (ref "SV1") (pin "3") (pinfunction "3_3") (pintype "passive"))
      (node (ref "SV2") (pin "3") (pinfunction "3_3") (pintype "passive"))
      (node (ref "SV3") (pin "3") (pinfunction "3_3") (pintype "passive"))
      (node (ref "SV4") (pin "3") (pinfunction "3_3") (pintype "passive"))
      (node (ref "SV5") (pin "3") (pinfunction "3_3") (pintype "passive"))
      (node (ref "SV6") (pin "3") (pinfunction "3_3") (pintype "passive"))
    )
    (net (code "43") (name "TOF_SDA") (class "Default")
      (node (ref "IC1") (pin "93") (pinfunction "PB7_93") (pintype "bidirectional"))
      (node (ref "SV1") (pin "4") (pinfunction "4_4") (pintype "passive"))
      (node (ref "SV2") (pin "4") (pinfunction "4_4") (pintype "passive"))
      (node (ref "SV3") (pin "4") (pinfunction "4_4") (pintype "passive"))
      (node (ref "SV4") (pin "4") (pinfunction "4_4") (pintype "passive"))
      (node (ref "SV5") (pin "4") (pinfunction "4_4") (pintype "passive"))
      (node (ref "SV6") (pin "4") (pinfunction "4_4") (pintype "passive"))
    )
    (net (code "44") (name "VCAP") (class "Default")
      (node (ref "C13") (pin "1") (pinfunction "1_1") (pintype "passive"))
      (node (ref "C14") (pin "1") (pinfunction "1_1") (pintype "passive"))
      (node (ref "IC1") (pin "48") (pinfunction "VCAP_1_48") (pintype "bidirectional"))
    )
    (net (code "45") (name "VCAP_2") (class "Default")
      (node (ref "C16") (pin "1") (pinfunction "1_1") (pintype "passive"))
      (node (ref "C17") (pin "1") (pinfunction "1_1") (pintype "passive"))
      (node (ref "IC1") (pin "73") (pinfunction "VCAP_2_73") (pintype "bidirectional"))
    )
    (net (code "46") (name "VCP_RX") (class "Default")
      (node (ref "IC1") (pin "23") (pinfunction "PA1_23") (pintype "bidirectional"))
      (node (ref "J1") (pin "13") (pinfunction "13_13") (pintype "passive"))
    )
    (net (code "47") (name "VCP_TX") (class "Default")
      (node (ref "IC1") (pin "22") (pinfunction "PA0_22") (pintype "bidirectional"))
      (node (ref "J1") (pin "14") (pinfunction "14_14") (pintype "passive"))
    )
    (net (code "48") (name "VDDA") (class "Default")
      (node (ref "C10") (pin "1") (pinfunction "1_1") (pintype "passive"))
      (node (ref "C7") (pin "1") (pinfunction "1_1") (pintype "passive"))
      (node (ref "C8") (pin "1") (pinfunction "1_1") (pintype "passive"))
      (node (ref "C9") (pin "1") (pinfunction "1_1") (pintype "passive"))
      (node (ref "FB1") (pin "2") (pinfunction "2_2") (pintype "bidirectional"))
      (node (ref "IC1") (pin "20") (pinfunction "VREF+_20") (pintype "bidirectional"))
      (node (ref "IC1") (pin "21") (pinfunction "VDDA_21") (pintype "bidirectional"))
    )
    (net (code "49") (name "VOUT_TOF1") (class "Default")
      (node (ref "SV1") (pin "7") (pinfunction "7_7") (pintype "passive"))
    )
    (net (code "50") (name "VOUT_TOF2") (class "Default")
      (node (ref "SV2") (pin "7") (pinfunction "7_7") (pintype "passive"))
    )
    (net (code "51") (name "VOUT_TOF3") (class "Default")
      (node (ref "SV3") (pin "7") (pinfunction "7_7") (pintype "passive"))
    )
    (net (code "52") (name "VOUT_TOF4") (class "Default")
      (node (ref "SV4") (pin "7") (pinfunction "7_7") (pintype "passive"))
    )
    (net (code "53") (name "VOUT_TOF5") (class "Default")
      (node (ref "SV5") (pin "7") (pinfunction "7_7") (pintype "passive"))
    )
    (net (code "54") (name "VOUT_TOF6") (class "Default")
      (node (ref "SV6") (pin "7") (pinfunction "7_7") (pintype "passive"))
    )
    (net (code "55") (name "V_BAT") (class "Default")
      (node (ref "D1") (pin "2") (pinfunction "A_2") (pintype "bidirectional"))
      (node (ref "U$6") (pin "P$1") (pinfunction "BAT+_P$1") (pintype "bidirectional"))
    )
    (net (code "56") (name "V_LS_1") (class "Default")
      (node (ref "CZ1") (pin "KOLEKTOR") (pinfunction "KOLEKTOR_KOLEKTOR") (pintype "bidirectional"))
      (node (ref "IC1") (pin "28") (pinfunction "PA4_28") (pintype "bidirectional"))
      (node (ref "R5") (pin "1") (pinfunction "1_1") (pintype "passive"))
    )
    (net (code "57") (name "V_LS_2") (class "Default")
      (node (ref "CZ2") (pin "KOLEKTOR") (pinfunction "KOLEKTOR_KOLEKTOR") (pintype "bidirectional"))
      (node (ref "IC1") (pin "29") (pinfunction "PA5_29") (pintype "bidirectional"))
      (node (ref "R7") (pin "1") (pinfunction "1_1") (pintype "passive"))
    )
    (net (code "58") (name "V_LS_3") (class "Default")
      (node (ref "CZ3") (pin "KOLEKTOR") (pinfunction "KOLEKTOR_KOLEKTOR") (pintype "bidirectional"))
      (node (ref "IC1") (pin "30") (pinfunction "PA6_30") (pintype "bidirectional"))
      (node (ref "R9") (pin "1") (pinfunction "1_1") (pintype "passive"))
    )
    (net (code "59") (name "V_LS_4") (class "Default")
      (node (ref "CZ4") (pin "KOLEKTOR") (pinfunction "KOLEKTOR_KOLEKTOR") (pintype "bidirectional"))
      (node (ref "IC1") (pin "31") (pinfunction "PA7_31") (pintype "bidirectional"))
      (node (ref "R11") (pin "1") (pinfunction "1_1") (pintype "passive"))
    )
    (net (code "60") (name "XSHUT1") (class "Default")
      (node (ref "IC1") (pin "5") (pinfunction "PE6_5") (pintype "bidirectional"))
      (node (ref "SV1") (pin "2") (pinfunction "2_2") (pintype "passive"))
    )
    (net (code "61") (name "XSHUT2") (class "Default")
      (node (ref "IC1") (pin "71") (pinfunction "PA12_71") (pintype "bidirectional"))
      (node (ref "SV2") (pin "2") (pinfunction "2_2") (pintype "passive"))
    )
    (net (code "62") (name "XSHUT3") (class "Default")
      (node (ref "IC1") (pin "38") (pinfunction "PE8_38") (pintype "bidirectional"))
      (node (ref "SV3") (pin "2") (pinfunction "2_2") (pintype "passive"))
    )
    (net (code "63") (name "XSHUT4") (class "Default")
      (node (ref "IC1") (pin "46") (pinfunction "PB10_46") (pintype "bidirectional"))
      (node (ref "SV4") (pin "2") (pinfunction "2_2") (pintype "passive"))
    )
    (net (code "64") (name "XSHUT5") (class "Default")
      (node (ref "IC1") (pin "79") (pinfunction "PC11_79") (pintype "bidirectional"))
      (node (ref "SV5") (pin "2") (pinfunction "2_2") (pintype "passive"))
    )
    (net (code "65") (name "XSHUT6") (class "Default")
      (node (ref "IC1") (pin "81") (pinfunction "PD0_81") (pintype "bidirectional"))
      (node (ref "SV6") (pin "2") (pinfunction "2_2") (pintype "passive"))
    )
    (net (code "66") (name "unconnected-(IC1-PA2-Pad24)") (class "Default")
      (node (ref "IC1") (pin "24") (pinfunction "PA2_24") (pintype "bidirectional"))
    )
    (net (code "67") (name "unconnected-(IC1-PA3-Pad25)") (class "Default")
      (node (ref "IC1") (pin "25") (pinfunction "PA3_25") (pintype "bidirectional"))
    )
    (net (code "68") (name "unconnected-(IC1-PA10-Pad69)") (class "Default")
      (node (ref "IC1") (pin "69") (pinfunction "PA10_69") (pintype "bidirectional"))
    )
    (net (code "69") (name "unconnected-(IC1-PA15-Pad77)") (class "Default")
      (node (ref "IC1") (pin "77") (pinfunction "PA15_77") (pintype "bidirectional"))
    )
    (net (code "70") (name "unconnected-(IC1-PB1-Pad35)") (class "Default")
      (node (ref "IC1") (pin "35") (pinfunction "PB1_35") (pintype "bidirectional"))
    )
    (net (code "71") (name "unconnected-(IC1-PB2-Pad36)") (class "Default")
      (node (ref "IC1") (pin "36") (pinfunction "PB2_36") (pintype "bidirectional"))
    )
    (net (code "72") (name "unconnected-(IC1-PB4-Pad90)") (class "Default")
      (node (ref "IC1") (pin "90") (pinfunction "PB4_90") (pintype "bidirectional"))
    )
    (net (code "73") (name "unconnected-(IC1-PB5-Pad91)") (class "Default")
      (node (ref "IC1") (pin "91") (pinfunction "PB5_91") (pintype "bidirectional"))
    )
    (net (code "74") (name "unconnected-(IC1-PB8-Pad95)") (class "Default")
      (node (ref "IC1") (pin "95") (pinfunction "PB8_95") (pintype "bidirectional"))
    )
    (net (code "75") (name "unconnected-(IC1-PB9-Pad96)") (class "Default")
      (node (ref "IC1") (pin "96") (pinfunction "PB9_96") (pintype "bidirectional"))
    )
    (net (code "76") (name "unconnected-(IC1-PB11-Pad47)") (class "Default")
      (node (ref "IC1") (pin "47") (pinfunction "PB11_47") (pintype "bidirectional"))
    )
    (net (code "77") (name "unconnected-(IC1-PB12-Pad51)") (class "Default")
      (node (ref "IC1") (pin "51") (pinfunction "PB12_51") (pintype "bidirectional"))
    )
    (net (code "78") (name "unconnected-(IC1-PC0-Pad15)") (class "Default")
      (node (ref "IC1") (pin "15") (pinfunction "PC0_15") (pintype "bidirectional"))
    )
    (net (code "79") (name "unconnected-(IC1-PC1-Pad16)") (class "Default")
      (node (ref "IC1") (pin "16") (pinfunction "PC1_16") (pintype "bidirectional"))
    )
    (net (code "80") (name "unconnected-(IC1-PC2_C-Pad17)") (class "Default")
      (node (ref "IC1") (pin "17") (pinfunction "PC2_C_17") (pintype "bidirectional"))
    )
    (net (code "81") (name "unconnected-(IC1-PC3_C-Pad18)") (class "Default")
      (node (ref "IC1") (pin "18") (pinfunction "PC3_C_18") (pintype "bidirectional"))
    )
    (net (code "82") (name "unconnected-(IC1-PC4-Pad32)") (class "Default")
      (node (ref "IC1") (pin "32") (pinfunction "PC4_32") (pintype "bidirectional"))
    )
    (net (code "83") (name "unconnected-(IC1-PC5-Pad33)") (class "Default")
      (node (ref "IC1") (pin "33") (pinfunction "PC5_33") (pintype "bidirectional"))
    )
    (net (code "84") (name "unconnected-(IC1-PC8-Pad65)") (class "Default")
      (node (ref "IC1") (pin "65") (pinfunction "PC8_65") (pintype "bidirectional"))
    )
    (net (code "85") (name "unconnected-(IC1-PC9-Pad66)") (class "Default")
      (node (ref "IC1") (pin "66") (pinfunction "PC9_66") (pintype "bidirectional"))
    )
    (net (code "86") (name "unconnected-(IC1-PC13-Pad7)") (class "Default")
      (node (ref "IC1") (pin "7") (pinfunction "PC13_7") (pintype "bidirectional"))
    )
    (net (code "87") (name "unconnected-(IC1-PC14-OSC32_IN-Pad8)") (class "Default")
      (node (ref "IC1") (pin "8") (pinfunction "PC14-OSC32_IN_8") (pintype "bidirectional"))
    )
    (net (code "88") (name "unconnected-(IC1-PC15-OSC32_OUT-Pad9)") (class "Default")
      (node (ref "IC1") (pin "9") (pinfunction "PC15-OSC32_OUT_9") (pintype "bidirectional"))
    )
    (net (code "89") (name "unconnected-(IC1-PD1-Pad82)") (class "Default")
      (node (ref "IC1") (pin "82") (pinfunction "PD1_82") (pintype "bidirectional"))
    )
    (net (code "90") (name "unconnected-(IC1-PD2-Pad83)") (class "Default")
      (node (ref "IC1") (pin "83") (pinfunction "PD2_83") (pintype "bidirectional"))
    )
    (net (code "91") (name "unconnected-(IC1-PD3-Pad84)") (class "Default")
      (node (ref "IC1") (pin "84") (pinfunction "PD3_84") (pintype "bidirectional"))
    )
    (net (code "92") (name "unconnected-(IC1-PD4-Pad85)") (class "Default")
      (node (ref "IC1") (pin "85") (pinfunction "PD4_85") (pintype "bidirectional"))
    )
    (net (code "93") (name "unconnected-(IC1-PD5-Pad86)") (class "Default")
      (node (ref "IC1") (pin "86") (pinfunction "PD5_86") (pintype "bidirectional"))
    )
    (net (code "94") (name "unconnected-(IC1-PD6-Pad87)") (class "Default")
      (node (ref "IC1") (pin "87") (pinfunction "PD6_87") (pintype "bidirectional"))
    )
    (net (code "95") (name "unconnected-(IC1-PD7-Pad88)") (class "Default")
      (node (ref "IC1") (pin "88") (pinfunction "PD7_88") (pintype "bidirectional"))
    )
    (net (code "96") (name "unconnected-(IC1-PD8-Pad55)") (class "Default")
      (node (ref "IC1") (pin "55") (pinfunction "PD8_55") (pintype "bidirectional"))
    )
    (net (code "97") (name "unconnected-(IC1-PD9-Pad56)") (class "Default")
      (node (ref "IC1") (pin "56") (pinfunction "PD9_56") (pintype "bidirectional"))
    )
    (net (code "98") (name "unconnected-(IC1-PD10-Pad57)") (class "Default")
      (node (ref "IC1") (pin "57") (pinfunction "PD10_57") (pintype "bidirectional"))
    )
    (net (code "99") (name "unconnected-(IC1-PE0-Pad97)") (class "Default")
      (node (ref "IC1") (pin "97") (pinfunction "PE0_97") (pintype "bidirectional"))
    )
    (net (code "100") (name "unconnected-(IC1-PE1-Pad98)") (class "Default")
      (node (ref "IC1") (pin "98") (pinfunction "PE1_98") (pintype "bidirectional"))
    )
    (net (code "101") (name "unconnected-(IC1-PE2-Pad1)") (class "Default")
      (node (ref "IC1") (pin "1") (pinfunction "PE2_1") (pintype "bidirectional"))
    )
    (net (code "102") (name "unconnected-(IC1-PE3-Pad2)") (class "Default")
      (node (ref "IC1") (pin "2") (pinfunction "PE3_2") (pintype "bidirectional"))
    )
    (net (code "103") (name "unconnected-(IC1-PE4-Pad3)") (class "Default")
      (node (ref "IC1") (pin "3") (pinfunction "PE4_3") (pintype "bidirectional"))
    )
    (net (code "104") (name "unconnected-(IC1-PE9-Pad39)") (class "Default")
      (node (ref "IC1") (pin "39") (pinfunction "PE9_39") (pintype "bidirectional"))
    )
    (net (code "105") (name "unconnected-(IC1-PE10-Pad40)") (class "Default")
      (node (ref "IC1") (pin "40") (pinfunction "PE10_40") (pintype "bidirectional"))
    )
    (net (code "106") (name "unconnected-(IC1-PE11-Pad41)") (class "Default")
      (node (ref "IC1") (pin "41") (pinfunction "PE11_41") (pintype "bidirectional"))
    )
    (net (code "107") (name "unconnected-(IC1-PE12-Pad42)") (class "Default")
      (node (ref "IC1") (pin "42") (pinfunction "PE12_42") (pintype "bidirectional"))
    )
    (net (code "108") (name "unconnected-(IC1-PE13-Pad43)") (class "Default")
      (node (ref "IC1") (pin "43") (pinfunction "PE13_43") (pintype "bidirectional"))
    )
    (net (code "109") (name "unconnected-(IC1-PE14-Pad44)") (class "Default")
      (node (ref "IC1") (pin "44") (pinfunction "PE14_44") (pintype "bidirectional"))
    )
    (net (code "110") (name "unconnected-(IC1-PH1-OSC_OUT-Pad13)") (class "Default")
      (node (ref "IC1") (pin "13") (pinfunction "PH1-OSC_OUT_13") (pintype "bidirectional"))
    )
    (net (code "111") (name "unconnected-(IC1-VBAT-Pad6)") (class "Default")
      (node (ref "IC1") (pin "6") (pinfunction "VBAT_6") (pintype "bidirectional"))
    )
    (net (code "112") (name "unconnected-(IC1-VSSA-Pad19)") (class "Default")
      (node (ref "IC1") (pin "19") (pinfunction "VSSA_19") (pintype "bidirectional"))
    )
    (net (code "113") (name "unconnected-(J1-Pad01)") (class "Default")
      (node (ref "J1") (pin "01") (pinfunction "01_01") (pintype "passive"))
    )
    (net (code "114") (name "unconnected-(J1-Pad02)") (class "Default")
      (node (ref "J1") (pin "02") (pinfunction "02_02") (pintype "passive"))
    )
    (net (code "115") (name "unconnected-(J1-Pad09)") (class "Default")
      (node (ref "J1") (pin "09") (pinfunction "09_09") (pintype "passive"))
    )
    (net (code "116") (name "unconnected-(J1-Pad10)") (class "Default")
      (node (ref "J1") (pin "10") (pinfunction "10_10") (pintype "passive"))
    )
    (net (code "117") (name "unconnected-(U$3-NC-Pad10)") (class "Default")
      (node (ref "U$3") (pin "10") (pinfunction "NC_10") (pintype "no_connect"))
    )
    (net (code "118") (name "unconnected-(U$3-NC_2-Pad28)") (class "Default")
      (node (ref "U$3") (pin "28") (pinfunction "NC_2_28") (pintype "no_connect"))
    )
  )
)
